# USB.net
KiCad netlist of a schematic drawn in Altium Designer
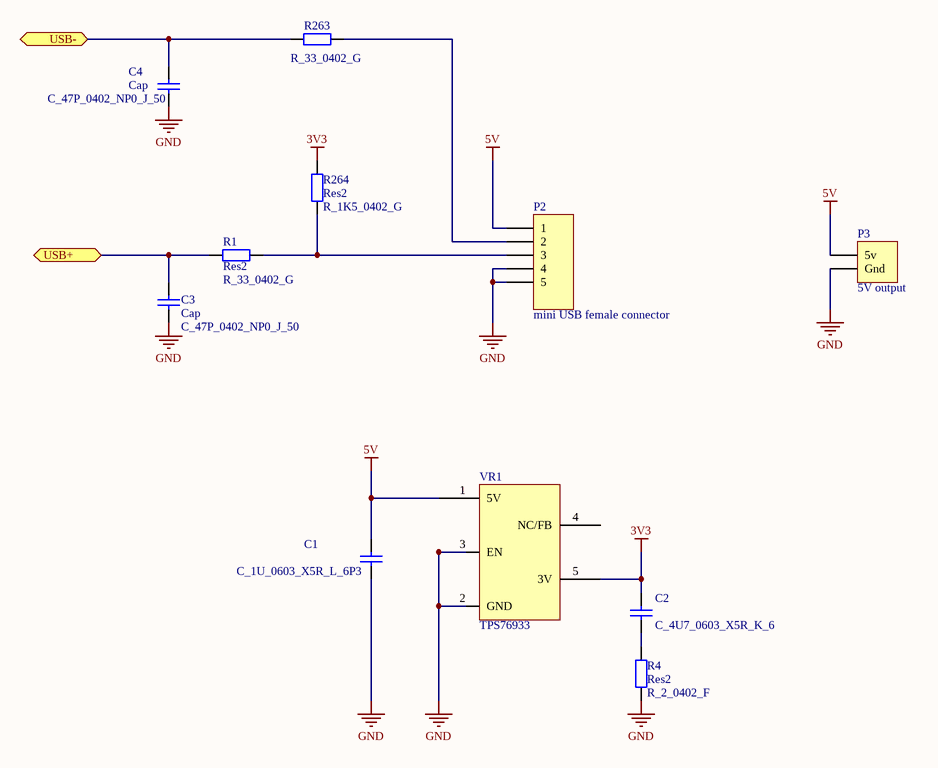
[diagram p0: USB.SchDoc]

(export (version "E")
  (design (tool "Eeschema 10.0.6"))
  (components
    (comp (ref "C1")
      (value "C_1U_0603_X5R_L_6P3")
      (footprint "C_0603")
      (description "Capacitor")
      (fields (field (name "Comment") "Cap") (field (name "PUBLISHER") "Altium Limited"))
      (libsource (lib "Miscellaneous Devices") (part "Cap"))
    )
    (comp (ref "C2")
      (value "C_4U7_0603_X5R_K_6")
      (footprint "C_0603")
      (description "Capacitor")
      (fields (field (name "Comment") "Cap") (field (name "PUBLISHER") "Altium Limited"))
      (libsource (lib "Miscellaneous Devices") (part "Cap"))
    )
    (comp (ref "C3")
      (value "Cap")
      (footprint "C_0402")
      (description "Capacitor")
      (fields (field (name "ALTIUM_VALUE") "C_47P_0402_NP0_J_50") (field (name "PUBLISHER") "Altium Limited"))
      (libsource (lib "Miscellaneous Devices") (part "Cap"))
    )
    (comp (ref "C4")
      (value "Cap")
      (footprint "C_0402")
      (description "Capacitor")
      (fields (field (name "ALTIUM_VALUE") "C_47P_0402_NP0_J_50") (field (name "PUBLISHER") "Altium Limited"))
      (libsource (lib "Miscellaneous Devices") (part "Cap"))
    )
    (comp (ref "P2")
      (value "mini USB female connector")
      (footprint "MicroUSB10118193")
      (description "USB connector")
      (fields (field (name "PUBLISHER") "Altium Limited"))
      (libsource (lib "Miscellaneous Connectors") (part "Header 6"))
    )
    (comp (ref "P3")
      (value "5V output")
      (footprint "Charger Board Connector Female")
      (description "5V output to charge BrewBit")
      (fields (field (name "PUBLISHER") "Altium Limited"))
      (libsource (lib "Miscellaneous Connectors") (part "Header 2"))
    )
    (comp (ref "R1")
      (value "Res2")
      (footprint "R_0402")
      (description "Resistor")
      (fields (field (name "ALTIUM_VALUE") "R_33_0402_G") (field (name "PUBLISHER") "Altium Limited"))
      (libsource (lib "") (part "Res2_2"))
    )
    (comp (ref "R4")
      (value "Res2")
      (footprint "R_0402")
      (description "Resistor")
      (fields (field (name "ALTIUM_VALUE") "R_2_0402_F") (field (name "PUBLISHER") "Altium Limited"))
      (libsource (lib "") (part "Res2_3"))
    )
    (comp (ref "R263")
      (value "R_33_0402_G")
      (footprint "R_0402")
      (description "Resistor")
      (fields (field (name "Comment") "Res2") (field (name "PUBLISHER") "Altium Limited"))
      (libsource (lib "") (part "Res2_1"))
    )
    (comp (ref "R264")
      (value "Res2")
      (footprint "R_0402")
      (description "Resistor")
      (fields (field (name "ALTIUM_VALUE") "R_1K5_0402_G") (field (name "PUBLISHER") "Altium Limited"))
      (libsource (lib "Miscellaneous Devices") (part "Res2"))
    )
    (comp (ref "VR1")
      (value "TPS76933")
      (footprint "TPS76933")
      (description "IC REG LDO 3.3V .1A SOT-23-5")
      (libsource (lib "CPUboard") (part "TPS76933"))
    )
  )
  (nets
    (net (code "1") (name "/USB+") (class "Default")
      (node (ref "C3") (pin "2") (pinfunction "2_2") (pintype "passive"))
      (node (ref "R1") (pin "1") (pinfunction "1_1") (pintype "passive"))
    )
    (net (code "2") (name "/USB-") (class "Default")
      (node (ref "C4") (pin "2") (pinfunction "2_2") (pintype "passive"))
      (node (ref "R263") (pin "2") (pinfunction "2_2") (pintype "passive"))
    )
    (net (code "3") (name "3V3") (class "Default")
      (node (ref "C2") (pin "1") (pinfunction "1_1") (pintype "passive"))
      (node (ref "R264") (pin "1") (pinfunction "1_1") (pintype "passive"))
      (node (ref "VR1") (pin "5") (pinfunction "3V_5") (pintype "passive"))
    )
    (net (code "4") (name "5V") (class "Default")
      (node (ref "C1") (pin "1") (pinfunction "1_1") (pintype "passive"))
      (node (ref "P2") (pin "1") (pinfunction "1_1") (pintype "passive"))
      (node (ref "P3") (pin "2") (pinfunction "5v_2") (pintype "passive"))
      (node (ref "VR1") (pin "1") (pinfunction "5V_1") (pintype "passive"))
    )
    (net (code "5") (name "GND") (class "Default")
      (node (ref "C1") (pin "2") (pinfunction "2_2") (pintype "passive"))
      (node (ref "C3") (pin "1") (pinfunction "1_1") (pintype "passive"))
      (node (ref "C4") (pin "1") (pinfunction "1_1") (pintype "passive"))
      (node (ref "P2") (pin "4") (pinfunction "4_4") (pintype "passive"))
      (node (ref "P2") (pin "5") (pinfunction "5_5") (pintype "passive"))
      (node (ref "P3") (pin "3") (pinfunction "Gnd_3") (pintype "passive"))
      (node (ref "R4") (pin "1") (pinfunction "1_1") (pintype "passive"))
      (node (ref "VR1") (pin "2") (pinfunction "GND_2") (pintype "passive"))
      (node (ref "VR1") (pin "3") (pinfunction "EN_3") (pintype "passive"))
    )
    (net (code "6") (name "Net-(C2-Pad2)") (class "Default")
      (node (ref "C2") (pin "2") (pinfunction "2_2") (pintype "passive"))
      (node (ref "R4") (pin "2") (pinfunction "2_2") (pintype "passive"))
    )
    (net (code "7") (name "Net-(P2-Pad2)") (class "Default")
      (node (ref "P2") (pin "2") (pinfunction "2_2") (pintype "passive"))
      (node (ref "R263") (pin "1") (pinfunction "1_1") (pintype "passive"))
    )
    (net (code "8") (name "Net-(P2-Pad3)") (class "Default")
      (node (ref "P2") (pin "3") (pinfunction "3_3") (pintype "passive"))
      (node (ref "R1") (pin "2") (pinfunction "2_2") (pintype "passive"))
      (node (ref "R264") (pin "2") (pinfunction "2_2") (pintype "passive"))
    )
    (net (code "9") (name "unconnected-(VR1-NC{slash}FB-Pad4)") (class "Default")
      (node (ref "VR1") (pin "4") (pinfunction "NC/FB_4") (pintype "passive"))
    )
  )
)
